# 4_Channel_ADC.net
KiCad netlist of a schematic drawn in Altium Designer
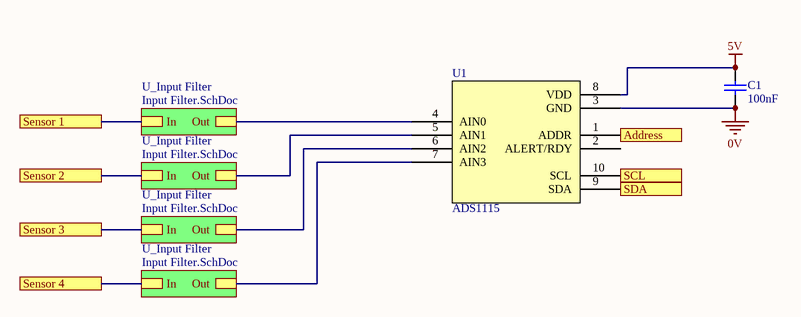
[diagram p0: 4 Channel ADC.SchDoc]

(export (version "E")
  (design (tool "Eeschema 10.0.6"))
  (components
    (comp (ref "C1")
      (value "100nF")
      (footprint "0805")
      (fields
        (field (name "PART NUMBER") "GCM21BR71E104KA37L")
        (field (name "TOLERANCE") "10%")
        (field (name "MANUFACTURER") "muRata")
      )
      (libsource (lib "ts_20-standard-library") (part "Capacitor"))
    )
    (comp (ref "U1")
      (value "ADS1115")
      (footprint "TI 10-VSSOP")
      (description "16 Bit Analog to Digital Converter 2, 4 Input 1 Sigma-Delta 10-VSSOP")
      (fields
        (field (name "MANUFACTURER") "Texas Instruments")
        (field (name "DIGIKEY PART NUMBER") "296-38849-1-ND")
      )
      (libsource (lib "ts_20-standard-library") (part "ADS1115"))
    )
  )
  (nets
    (net (code "1") (name "/Address") (class "Default")
      (node (ref "U1") (pin "1") (pinfunction "ADDR_1") (pintype "passive"))
    )
    (net (code "2") (name "/Out") (class "Default")
      (node (ref "U1") (pin "4") (pinfunction "AIN0_4") (pintype "passive"))
    )
    (net (code "3") (name "/Out_1") (class "Default")
      (node (ref "U1") (pin "6") (pinfunction "AIN2_6") (pintype "passive"))
    )
    (net (code "4") (name "/Out_2") (class "Default")
      (node (ref "U1") (pin "7") (pinfunction "AIN3_7") (pintype "passive"))
    )
    (net (code "5") (name "/Out_3") (class "Default")
      (node (ref "U1") (pin "5") (pinfunction "AIN1_5") (pintype "passive"))
    )
    (net (code "6") (name "/SCL") (class "Default")
      (node (ref "U1") (pin "10") (pinfunction "SCL_10") (pintype "passive"))
    )
    (net (code "7") (name "/SDA") (class "Default")
      (node (ref "U1") (pin "9") (pinfunction "SDA_9") (pintype "passive"))
    )
    (net (code "12") (name "0V") (class "Default")
      (node (ref "C1") (pin "1") (pinfunction "1_1") (pintype "passive"))
      (node (ref "U1") (pin "3") (pinfunction "GND_3") (pintype "passive"))
    )
    (net (code "13") (name "5V") (class "Default")
      (node (ref "C1") (pin "2") (pinfunction "2_2") (pintype "passive"))
      (node (ref "U1") (pin "8") (pinfunction "VDD_8") (pintype "passive"))
    )
    (net (code "14") (name "unconnected-(U1-ALERT{slash}RDY-Pad2)") (class "Default")
      (node (ref "U1") (pin "2") (pinfunction "ALERT/RDY_2") (pintype "passive"))
    )
  )
)
